# Sheet1.net
KiCad netlist of a schematic drawn in Altium Designer
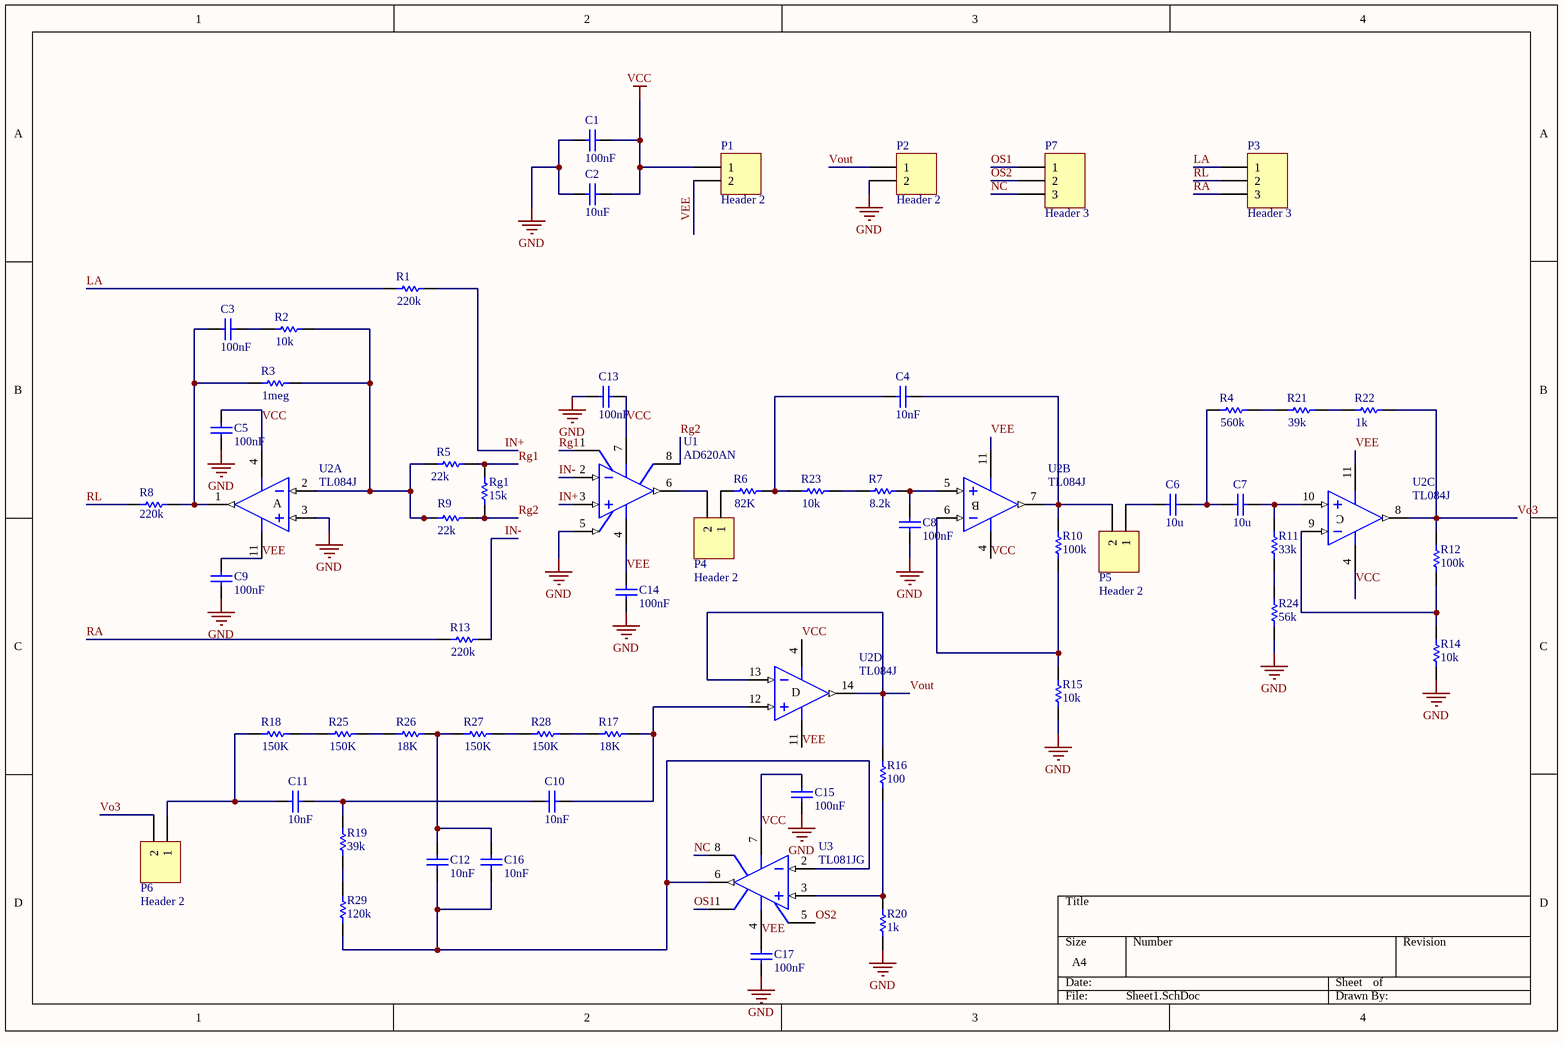
[diagram p0: Sheet1.SchDoc]

(export (version "E")
  (design (tool "Eeschema 10.0.6"))
  (components
    (comp (ref "C1")
      (value "100nF")
      (footprint "RAD-0.3")
      (description "Capacitor")
      (fields (field (name "PUBLISHER") "Altium Limited"))
      (libsource (lib "Miscellaneous Devices") (part "Cap"))
    )
    (comp (ref "C2")
      (value "10uF")
      (footprint "RAD-0.3")
      (description "Capacitor")
      (fields (field (name "PUBLISHER") "Altium Limited"))
      (libsource (lib "Miscellaneous Devices") (part "Cap"))
    )
    (comp (ref "C3")
      (value "100nF")
      (footprint "RAD-0.3")
      (description "Capacitor")
      (fields (field (name "PUBLISHER") "Altium Limited"))
      (libsource (lib "Miscellaneous Devices") (part "Cap"))
    )
    (comp (ref "C4")
      (value "10nF")
      (footprint "RAD-0.3")
      (description "Capacitor")
      (fields (field (name "Comment") "Cap") (field (name "PUBLISHER") "Altium Limited"))
      (libsource (lib "Miscellaneous Devices") (part "Cap"))
    )
    (comp (ref "C5")
      (value "100nF")
      (footprint "RAD-0.3")
      (description "Capacitor")
      (fields (field (name "Comment") "Cap") (field (name "PUBLISHER") "Altium Limited"))
      (libsource (lib "Miscellaneous Devices") (part "Cap"))
    )
    (comp (ref "C6")
      (value "10u")
      (footprint "RAD-0.3")
      (description "Capacitor")
      (fields (field (name "Comment") "Cap") (field (name "PUBLISHER") "Altium Limited"))
      (libsource (lib "Miscellaneous Devices") (part "Cap"))
    )
    (comp (ref "C7")
      (value "10u")
      (footprint "RAD-0.3")
      (description "Capacitor")
      (fields (field (name "Comment") "Cap") (field (name "PUBLISHER") "Altium Limited"))
      (libsource (lib "Miscellaneous Devices") (part "Cap"))
    )
    (comp (ref "C8")
      (value "100nF")
      (footprint "RAD-0.3")
      (description "Capacitor")
      (fields (field (name "Comment") "Cap") (field (name "PUBLISHER") "Altium Limited"))
      (libsource (lib "Miscellaneous Devices") (part "Cap"))
    )
    (comp (ref "C9")
      (value "100nF")
      (footprint "RAD-0.3")
      (description "Capacitor")
      (fields (field (name "Comment") "Cap") (field (name "PUBLISHER") "Altium Limited"))
      (libsource (lib "Miscellaneous Devices") (part "Cap"))
    )
    (comp (ref "C10")
      (value "10nF")
      (footprint "RAD-0.3")
      (description "Capacitor")
      (fields (field (name "Comment") "Cap") (field (name "PUBLISHER") "Altium Limited"))
      (libsource (lib "Miscellaneous Devices") (part "Cap"))
    )
    (comp (ref "C11")
      (value "10nF")
      (footprint "RAD-0.3")
      (description "Capacitor")
      (fields (field (name "Comment") "Cap") (field (name "PUBLISHER") "Altium Limited"))
      (libsource (lib "Miscellaneous Devices") (part "Cap"))
    )
    (comp (ref "C12")
      (value "10nF")
      (footprint "RAD-0.3")
      (description "Capacitor")
      (fields (field (name "Comment") "Cap") (field (name "PUBLISHER") "Altium Limited"))
      (libsource (lib "Miscellaneous Devices") (part "Cap"))
    )
    (comp (ref "C13")
      (value "100nF")
      (footprint "RAD-0.3")
      (description "Capacitor")
      (fields (field (name "PUBLISHER") "Altium Limited"))
      (libsource (lib "Miscellaneous Devices") (part "Cap"))
    )
    (comp (ref "C14")
      (value "100nF")
      (footprint "RAD-0.3")
      (description "Capacitor")
      (fields (field (name "Comment") "Cap") (field (name "PUBLISHER") "Altium Limited"))
      (libsource (lib "Miscellaneous Devices") (part "Cap"))
    )
    (comp (ref "C15")
      (value "100nF")
      (footprint "RAD-0.3")
      (description "Capacitor")
      (fields (field (name "Comment") "Cap") (field (name "PUBLISHER") "Altium Limited"))
      (libsource (lib "Miscellaneous Devices") (part "Cap"))
    )
    (comp (ref "C16")
      (value "10nF")
      (footprint "RAD-0.3")
      (description "Capacitor")
      (fields (field (name "Comment") "Cap") (field (name "PUBLISHER") "Altium Limited"))
      (libsource (lib "Miscellaneous Devices") (part "Cap"))
    )
    (comp (ref "C17")
      (value "100nF")
      (footprint "RAD-0.3")
      (description "Capacitor")
      (fields (field (name "Comment") "Cap") (field (name "PUBLISHER") "Altium Limited"))
      (libsource (lib "Miscellaneous Devices") (part "Cap"))
    )
    (comp (ref "P1")
      (value "Header 2")
      (footprint "HDR1X2")
      (description "Header, 2-Pin")
      (fields (field (name "PUBLISHER") "Altium Limited"))
      (libsource (lib "") (part "Header 2_1"))
    )
    (comp (ref "P2")
      (value "Header 2")
      (footprint "HDR1X2")
      (description "Header, 2-Pin")
      (fields (field (name "PUBLISHER") "Altium Limited"))
      (libsource (lib "") (part "Header 2_1"))
    )
    (comp (ref "P3")
      (value "Header 3")
      (footprint "HDR1X3")
      (description "Header, 3-Pin")
      (fields (field (name "PUBLISHER") "Altium Limited"))
      (libsource (lib "Miscellaneous Connectors") (part "Header 3"))
    )
    (comp (ref "P4")
      (value "Header 2")
      (footprint "HDR1X2")
      (description "Header, 2-Pin")
      (fields (field (name "PUBLISHER") "Altium Limited"))
      (libsource (lib "Miscellaneous Connectors") (part "Header 2"))
    )
    (comp (ref "P5")
      (value "Header 2")
      (footprint "HDR1X2")
      (description "Header, 2-Pin")
      (fields (field (name "PUBLISHER") "Altium Limited"))
      (libsource (lib "Miscellaneous Connectors") (part "Header 2"))
    )
    (comp (ref "P6")
      (value "Header 2")
      (footprint "HDR1X2")
      (description "Header, 2-Pin")
      (fields (field (name "PUBLISHER") "Altium Limited"))
      (libsource (lib "Miscellaneous Connectors") (part "Header 2"))
    )
    (comp (ref "P7")
      (value "Header 3")
      (footprint "HDR1X3")
      (description "Header, 3-Pin")
      (fields (field (name "PUBLISHER") "Altium Limited"))
      (libsource (lib "Miscellaneous Connectors") (part "Header 3"))
    )
    (comp (ref "R1")
      (value "220k")
      (footprint "AXIAL-0.3")
      (description "Resistor")
      (fields (field (name "Comment") "Res1") (field (name "PUBLISHER") "Altium Limited"))
      (libsource (lib "Miscellaneous Devices") (part "Res1"))
    )
    (comp (ref "R2")
      (value "10k")
      (footprint "AXIAL-0.3")
      (description "Resistor")
      (fields (field (name "Comment") "Res1") (field (name "PUBLISHER") "Altium Limited"))
      (libsource (lib "Miscellaneous Devices") (part "Res1"))
    )
    (comp (ref "R3")
      (value "1meg")
      (footprint "AXIAL-0.3")
      (description "Resistor")
      (fields (field (name "Comment") "Res1") (field (name "PUBLISHER") "Altium Limited"))
      (libsource (lib "Miscellaneous Devices") (part "Res1"))
    )
    (comp (ref "R4")
      (value "560k")
      (footprint "AXIAL-0.3")
      (description "Resistor")
      (fields (field (name "Comment") "Res1") (field (name "PUBLISHER") "Altium Limited"))
      (libsource (lib "Miscellaneous Devices") (part "Res1"))
    )
    (comp (ref "R5")
      (value "22k")
      (footprint "AXIAL-0.3")
      (description "Resistor")
      (fields (field (name "Comment") "Res1") (field (name "PUBLISHER") "Altium Limited"))
      (libsource (lib "Miscellaneous Devices") (part "Res1"))
    )
    (comp (ref "R6")
      (value "82K")
      (footprint "AXIAL-0.3")
      (description "Resistor")
      (fields (field (name "Comment") "Res1") (field (name "PUBLISHER") "Altium Limited"))
      (libsource (lib "Miscellaneous Devices") (part "Res1"))
    )
    (comp (ref "R7")
      (value "8.2k")
      (footprint "AXIAL-0.3")
      (description "Resistor")
      (fields (field (name "Comment") "Res1") (field (name "PUBLISHER") "Altium Limited"))
      (libsource (lib "Miscellaneous Devices") (part "Res1"))
    )
    (comp (ref "R8")
      (value "220k")
      (footprint "AXIAL-0.3")
      (description "Resistor")
      (fields (field (name "Comment") "Res1") (field (name "PUBLISHER") "Altium Limited"))
      (libsource (lib "Miscellaneous Devices") (part "Res1"))
    )
    (comp (ref "R9")
      (value "22k")
      (footprint "AXIAL-0.3")
      (description "Resistor")
      (fields (field (name "Comment") "Res1") (field (name "PUBLISHER") "Altium Limited"))
      (libsource (lib "Miscellaneous Devices") (part "Res1"))
    )
    (comp (ref "R10")
      (value "100k")
      (footprint "AXIAL-0.3")
      (description "Resistor")
      (fields (field (name "Comment") "Res1") (field (name "PUBLISHER") "Altium Limited"))
      (libsource (lib "Miscellaneous Devices") (part "Res1"))
    )
    (comp (ref "R11")
      (value "33k")
      (footprint "AXIAL-0.3")
      (description "Resistor")
      (fields (field (name "Comment") "Res1") (field (name "PUBLISHER") "Altium Limited"))
      (libsource (lib "Miscellaneous Devices") (part "Res1"))
    )
    (comp (ref "R12")
      (value "100k")
      (footprint "AXIAL-0.3")
      (description "Resistor")
      (fields (field (name "Comment") "Res1") (field (name "PUBLISHER") "Altium Limited"))
      (libsource (lib "Miscellaneous Devices") (part "Res1"))
    )
    (comp (ref "R13")
      (value "220k")
      (footprint "AXIAL-0.3")
      (description "Resistor")
      (fields (field (name "Comment") "Res1") (field (name "PUBLISHER") "Altium Limited"))
      (libsource (lib "Miscellaneous Devices") (part "Res1"))
    )
    (comp (ref "R14")
      (value "10k")
      (footprint "AXIAL-0.3")
      (description "Resistor")
      (fields (field (name "Comment") "Res1") (field (name "PUBLISHER") "Altium Limited"))
      (libsource (lib "Miscellaneous Devices") (part "Res1"))
    )
    (comp (ref "R15")
      (value "10k")
      (footprint "AXIAL-0.3")
      (description "Resistor")
      (fields (field (name "Comment") "Res1") (field (name "PUBLISHER") "Altium Limited"))
      (libsource (lib "Miscellaneous Devices") (part "Res1"))
    )
    (comp (ref "R16")
      (value "100")
      (footprint "AXIAL-0.3")
      (description "Resistor")
      (fields (field (name "Comment") "Res1") (field (name "PUBLISHER") "Altium Limited"))
      (libsource (lib "Miscellaneous Devices") (part "Res1"))
    )
    (comp (ref "R17")
      (value "18K")
      (footprint "AXIAL-0.3")
      (description "Resistor")
      (fields (field (name "Comment") "Res1") (field (name "PUBLISHER") "Altium Limited"))
      (libsource (lib "Miscellaneous Devices") (part "Res1"))
    )
    (comp (ref "R18")
      (value "150K")
      (footprint "AXIAL-0.3")
      (description "Resistor")
      (fields (field (name "Comment") "Res1") (field (name "PUBLISHER") "Altium Limited"))
      (libsource (lib "Miscellaneous Devices") (part "Res1"))
    )
    (comp (ref "R19")
      (value "39k")
      (footprint "AXIAL-0.3")
      (description "Resistor")
      (fields (field (name "Comment") "Res1") (field (name "PUBLISHER") "Altium Limited"))
      (libsource (lib "Miscellaneous Devices") (part "Res1"))
    )
    (comp (ref "R20")
      (value "1k")
      (footprint "AXIAL-0.3")
      (description "Resistor")
      (fields (field (name "Comment") "Res1") (field (name "PUBLISHER") "Altium Limited"))
      (libsource (lib "Miscellaneous Devices") (part "Res1"))
    )
    (comp (ref "R21")
      (value "39k")
      (footprint "AXIAL-0.3")
      (description "Resistor")
      (fields (field (name "Comment") "Res1") (field (name "PUBLISHER") "Altium Limited"))
      (libsource (lib "Miscellaneous Devices") (part "Res1"))
    )
    (comp (ref "R22")
      (value "1k")
      (footprint "AXIAL-0.3")
      (description "Resistor")
      (fields (field (name "Comment") "Res1") (field (name "PUBLISHER") "Altium Limited"))
      (libsource (lib "Miscellaneous Devices") (part "Res1"))
    )
    (comp (ref "R23")
      (value "10k")
      (footprint "AXIAL-0.3")
      (description "Resistor")
      (fields (field (name "Comment") "Res1") (field (name "PUBLISHER") "Altium Limited"))
      (libsource (lib "Miscellaneous Devices") (part "Res1"))
    )
    (comp (ref "R24")
      (value "56k")
      (footprint "AXIAL-0.3")
      (description "Resistor")
      (fields (field (name "Comment") "Res1") (field (name "PUBLISHER") "Altium Limited"))
      (libsource (lib "Miscellaneous Devices") (part "Res1"))
    )
    (comp (ref "R25")
      (value "150K")
      (footprint "AXIAL-0.3")
      (description "Resistor")
      (fields (field (name "Comment") "Res1") (field (name "PUBLISHER") "Altium Limited"))
      (libsource (lib "Miscellaneous Devices") (part "Res1"))
    )
    (comp (ref "R26")
      (value "18K")
      (footprint "AXIAL-0.3")
      (description "Resistor")
      (fields (field (name "Comment") "Res1") (field (name "PUBLISHER") "Altium Limited"))
      (libsource (lib "Miscellaneous Devices") (part "Res1"))
    )
    (comp (ref "R27")
      (value "150K")
      (footprint "AXIAL-0.3")
      (description "Resistor")
      (fields (field (name "Comment") "Res1") (field (name "PUBLISHER") "Altium Limited"))
      (libsource (lib "Miscellaneous Devices") (part "Res1"))
    )
    (comp (ref "R28")
      (value "150K")
      (footprint "AXIAL-0.3")
      (description "Resistor")
      (fields (field (name "Comment") "Res1") (field (name "PUBLISHER") "Altium Limited"))
      (libsource (lib "Miscellaneous Devices") (part "Res1"))
    )
    (comp (ref "R29")
      (value "120k")
      (footprint "AXIAL-0.3")
      (description "Resistor")
      (fields (field (name "Comment") "Res1") (field (name "PUBLISHER") "Altium Limited"))
      (libsource (lib "Miscellaneous Devices") (part "Res1"))
    )
    (comp (ref "Rg1")
      (value "15k")
      (footprint "AXIAL-0.3")
      (description "Resistor")
      (fields (field (name "Comment") "Res1") (field (name "PUBLISHER") "Altium Limited"))
      (libsource (lib "Miscellaneous Devices") (part "Res1"))
    )
    (comp (ref "U1")
      (value "AD620AN")
      (footprint "N-8")
      (description "Low-Cost, Low-Power Instrumentation Amplifier")
      (fields (field (name "PUBLISHER") "Altium Limited"))
      (libsource (lib "AD Instrumentation Amplifier") (part "AD620AN"))
    )
    (comp (ref "U2")
      (value "TL084J")
      (footprint "J014")
      (description "JFET-Input Operational Amplifier")
      (fields (field (name "PUBLISHER") "Altium Limited"))
      (libsource (lib "TI Operational Amplifier") (part "TL084J"))
    )
    (comp (ref "U3")
      (value "TL081JG")
      (footprint "JG008")
      (description "JFET-Input Operational Amplifier")
      (fields (field (name "PUBLISHER") "Altium Limited"))
      (libsource (lib "TI Operational Amplifier") (part "TL081JG"))
    )
  )
  (nets
    (net (code "1") (name "/IN+") (class "Default")
      (node (ref "R1") (pin "2") (pinfunction "2_2") (pintype "passive"))
      (node (ref "U1") (pin "3") (pinfunction "+IN_3") (pintype "input"))
    )
    (net (code "2") (name "/IN-") (class "Default")
      (node (ref "R13") (pin "2") (pinfunction "2_2") (pintype "passive"))
      (node (ref "U1") (pin "2") (pinfunction "-IN_2") (pintype "input"))
    )
    (net (code "3") (name "/LA") (class "Default")
      (node (ref "P3") (pin "1") (pinfunction "1_1") (pintype "passive"))
      (node (ref "R1") (pin "1") (pinfunction "1_1") (pintype "passive"))
    )
    (net (code "4") (name "/NC") (class "Default")
      (node (ref "P7") (pin "3") (pinfunction "3_3") (pintype "passive"))
      (node (ref "U3") (pin "8") (pinfunction "NC_8") (pintype "passive"))
    )
    (net (code "5") (name "/OS1") (class "Default")
      (node (ref "P7") (pin "1") (pinfunction "1_1") (pintype "passive"))
      (node (ref "U3") (pin "1") (pinfunction "OS_TRIM_1") (pintype "passive"))
    )
    (net (code "6") (name "/OS2") (class "Default")
      (node (ref "P7") (pin "2") (pinfunction "2_2") (pintype "passive"))
      (node (ref "U3") (pin "5") (pinfunction "OS_TRIM_5") (pintype "passive"))
    )
    (net (code "7") (name "/RA") (class "Default")
      (node (ref "P3") (pin "3") (pinfunction "3_3") (pintype "passive"))
      (node (ref "R13") (pin "1") (pinfunction "1_1") (pintype "passive"))
    )
    (net (code "8") (name "/RL") (class "Default")
      (node (ref "P3") (pin "2") (pinfunction "2_2") (pintype "passive"))
      (node (ref "R8") (pin "2") (pinfunction "2_2") (pintype "passive"))
    )
    (net (code "9") (name "/Rg1") (class "Default")
      (node (ref "R5") (pin "2") (pinfunction "2_2") (pintype "passive"))
      (node (ref "Rg1") (pin "2") (pinfunction "2_2") (pintype "passive"))
      (node (ref "U1") (pin "1") (pinfunction "RG_1") (pintype "passive"))
    )
    (net (code "10") (name "/Rg2") (class "Default")
      (node (ref "R9") (pin "2") (pinfunction "2_2") (pintype "passive"))
      (node (ref "Rg1") (pin "1") (pinfunction "1_1") (pintype "passive"))
      (node (ref "U1") (pin "8") (pinfunction "RG_8") (pintype "passive"))
    )
    (net (code "11") (name "/VEE") (class "Default")
      (node (ref "C14") (pin "2") (pinfunction "2_2") (pintype "passive"))
      (node (ref "C17") (pin "2") (pinfunction "2_2") (pintype "passive"))
      (node (ref "C9") (pin "2") (pinfunction "2_2") (pintype "passive"))
      (node (ref "P1") (pin "2") (pinfunction "2_2") (pintype "passive"))
      (node (ref "U1") (pin "4") (pinfunction "V-_4") (pintype "power_in"))
      (node (ref "U2") (pin "11") (pinfunction "V-_11") (pintype "power_in"))
      (node (ref "U3") (pin "4") (pinfunction "V-_4") (pintype "power_in"))
    )
    (net (code "12") (name "/Vo3") (class "Default")
      (node (ref "P6") (pin "2") (pinfunction "2_2") (pintype "passive"))
      (node (ref "R12") (pin "2") (pinfunction "2_2") (pintype "passive"))
      (node (ref "R22") (pin "2") (pinfunction "2_2") (pintype "passive"))
      (node (ref "U2") (pin "8") (pinfunction "OUT_8") (pintype "output"))
    )
    (net (code "13") (name "/Vout") (class "Default")
      (node (ref "P2") (pin "1") (pinfunction "1_1") (pintype "passive"))
      (node (ref "R16") (pin "2") (pinfunction "2_2") (pintype "passive"))
      (node (ref "U2") (pin "13") (pinfunction "IN-_13") (pintype "input"))
      (node (ref "U2") (pin "14") (pinfunction "OUT_14") (pintype "output"))
    )
    (net (code "14") (name "GND") (class "Default")
      (node (ref "C1") (pin "1") (pinfunction "1_1") (pintype "passive"))
      (node (ref "C13") (pin "1") (pinfunction "1_1") (pintype "passive"))
      (node (ref "C14") (pin "1") (pinfunction "1_1") (pintype "passive"))
      (node (ref "C15") (pin "1") (pinfunction "1_1") (pintype "passive"))
      (node (ref "C17") (pin "1") (pinfunction "1_1") (pintype "passive"))
      (node (ref "C2") (pin "1") (pinfunction "1_1") (pintype "passive"))
      (node (ref "C5") (pin "1") (pinfunction "1_1") (pintype "passive"))
      (node (ref "C8") (pin "1") (pinfunction "1_1") (pintype "passive"))
      (node (ref "C9") (pin "1") (pinfunction "1_1") (pintype "passive"))
      (node (ref "P2") (pin "2") (pinfunction "2_2") (pintype "passive"))
      (node (ref "R14") (pin "1") (pinfunction "1_1") (pintype "passive"))
      (node (ref "R15") (pin "1") (pinfunction "1_1") (pintype "passive"))
      (node (ref "R20") (pin "1") (pinfunction "1_1") (pintype "passive"))
      (node (ref "R24") (pin "1") (pinfunction "1_1") (pintype "passive"))
      (node (ref "U1") (pin "5") (pinfunction "REF_5") (pintype "input"))
      (node (ref "U2") (pin "3") (pinfunction "IN+_3") (pintype "input"))
    )
    (net (code "15") (name "Net-(C3-Pad2)") (class "Default")
      (node (ref "C3") (pin "2") (pinfunction "2_2") (pintype "passive"))
      (node (ref "R2") (pin "1") (pinfunction "1_1") (pintype "passive"))
    )
    (net (code "16") (name "Net-(C4-Pad2)") (class "Default")
      (node (ref "C4") (pin "2") (pinfunction "2_2") (pintype "passive"))
      (node (ref "R23") (pin "1") (pinfunction "1_1") (pintype "passive"))
      (node (ref "R6") (pin "2") (pinfunction "2_2") (pintype "passive"))
    )
    (net (code "17") (name "Net-(C6-Pad1)") (class "Default")
      (node (ref "C6") (pin "1") (pinfunction "1_1") (pintype "passive"))
      (node (ref "C7") (pin "2") (pinfunction "2_2") (pintype "passive"))
      (node (ref "R4") (pin "1") (pinfunction "1_1") (pintype "passive"))
    )
    (net (code "18") (name "Net-(C6-Pad2)") (class "Default")
      (node (ref "C6") (pin "2") (pinfunction "2_2") (pintype "passive"))
      (node (ref "P5") (pin "1") (pinfunction "1_1") (pintype "passive"))
    )
    (net (code "19") (name "Net-(C10-Pad2)") (class "Default")
      (node (ref "C10") (pin "2") (pinfunction "2_2") (pintype "passive"))
      (node (ref "C11") (pin "1") (pinfunction "1_1") (pintype "passive"))
      (node (ref "R19") (pin "2") (pinfunction "2_2") (pintype "passive"))
    )
    (net (code "20") (name "Net-(C11-Pad2)") (class "Default")
      (node (ref "C11") (pin "2") (pinfunction "2_2") (pintype "passive"))
      (node (ref "P6") (pin "1") (pinfunction "1_1") (pintype "passive"))
      (node (ref "R18") (pin "1") (pinfunction "1_1") (pintype "passive"))
    )
    (net (code "21") (name "Net-(C12-Pad1)") (class "Default")
      (node (ref "C12") (pin "1") (pinfunction "1_1") (pintype "passive"))
      (node (ref "C16") (pin "1") (pinfunction "1_1") (pintype "passive"))
      (node (ref "R26") (pin "2") (pinfunction "2_2") (pintype "passive"))
      (node (ref "R27") (pin "1") (pinfunction "1_1") (pintype "passive"))
    )
    (net (code "22") (name "Net-(P4-Pad1)") (class "Default")
      (node (ref "P4") (pin "1") (pinfunction "1_1") (pintype "passive"))
      (node (ref "R6") (pin "1") (pinfunction "1_1") (pintype "passive"))
    )
    (net (code "23") (name "Net-(R11-Pad1)") (class "Default")
      (node (ref "R11") (pin "1") (pinfunction "1_1") (pintype "passive"))
      (node (ref "R24") (pin "2") (pinfunction "2_2") (pintype "passive"))
    )
    (net (code "24") (name "Net-(R17-Pad1)") (class "Default")
      (node (ref "R17") (pin "1") (pinfunction "1_1") (pintype "passive"))
      (node (ref "R28") (pin "2") (pinfunction "2_2") (pintype "passive"))
    )
    (net (code "25") (name "Net-(R18-Pad2)") (class "Default")
      (node (ref "R18") (pin "2") (pinfunction "2_2") (pintype "passive"))
      (node (ref "R25") (pin "1") (pinfunction "1_1") (pintype "passive"))
    )
    (net (code "26") (name "Net-(R19-Pad1)") (class "Default")
      (node (ref "R19") (pin "1") (pinfunction "1_1") (pintype "passive"))
      (node (ref "R29") (pin "2") (pinfunction "2_2") (pintype "passive"))
    )
    (net (code "27") (name "Net-(R21-Pad1)") (class "Default")
      (node (ref "R21") (pin "1") (pinfunction "1_1") (pintype "passive"))
      (node (ref "R4") (pin "2") (pinfunction "2_2") (pintype "passive"))
    )
    (net (code "28") (name "Net-(R21-Pad2)") (class "Default")
      (node (ref "R21") (pin "2") (pinfunction "2_2") (pintype "passive"))
      (node (ref "R22") (pin "1") (pinfunction "1_1") (pintype "passive"))
    )
    (net (code "29") (name "Net-(R23-Pad2)") (class "Default")
      (node (ref "R23") (pin "2") (pinfunction "2_2") (pintype "passive"))
      (node (ref "R7") (pin "1") (pinfunction "1_1") (pintype "passive"))
    )
    (net (code "30") (name "Net-(R25-Pad2)") (class "Default")
      (node (ref "R25") (pin "2") (pinfunction "2_2") (pintype "passive"))
      (node (ref "R26") (pin "1") (pinfunction "1_1") (pintype "passive"))
    )
    (net (code "31") (name "Net-(R27-Pad2)") (class "Default")
      (node (ref "R27") (pin "2") (pinfunction "2_2") (pintype "passive"))
      (node (ref "R28") (pin "1") (pinfunction "1_1") (pintype "passive"))
    )
    (net (code "32") (name "Net-(U1-OUT)") (class "Default")
      (node (ref "P4") (pin "2") (pinfunction "2_2") (pintype "passive"))
      (node (ref "U1") (pin "6") (pinfunction "OUT_6") (pintype "output"))
    )
    (net (code "33") (name "Net-(U2A-IN-)") (class "Default")
      (node (ref "R2") (pin "2") (pinfunction "2_2") (pintype "passive"))
      (node (ref "R3") (pin "2") (pinfunction "2_2") (pintype "passive"))
      (node (ref "R5") (pin "1") (pinfunction "1_1") (pintype "passive"))
      (node (ref "R9") (pin "1") (pinfunction "1_1") (pintype "passive"))
      (node (ref "U2") (pin "2") (pinfunction "IN-_2") (pintype "input"))
    )
    (net (code "34") (name "Net-(U2A-OUT)") (class "Default")
      (node (ref "C3") (pin "1") (pinfunction "1_1") (pintype "passive"))
      (node (ref "R3") (pin "1") (pinfunction "1_1") (pintype "passive"))
      (node (ref "R8") (pin "1") (pinfunction "1_1") (pintype "passive"))
      (node (ref "U2") (pin "1") (pinfunction "OUT_1") (pintype "output"))
    )
    (net (code "35") (name "Net-(U2B-IN+)") (class "Default")
      (node (ref "C8") (pin "2") (pinfunction "2_2") (pintype "passive"))
      (node (ref "R7") (pin "2") (pinfunction "2_2") (pintype "passive"))
      (node (ref "U2") (pin "5") (pinfunction "IN+_5") (pintype "input"))
    )
    (net (code "36") (name "Net-(U2B-IN-)") (class "Default")
      (node (ref "R10") (pin "1") (pinfunction "1_1") (pintype "passive"))
      (node (ref "R15") (pin "2") (pinfunction "2_2") (pintype "passive"))
      (node (ref "U2") (pin "6") (pinfunction "IN-_6") (pintype "input"))
    )
    (net (code "37") (name "Net-(U2B-OUT)") (class "Default")
      (node (ref "C4") (pin "1") (pinfunction "1_1") (pintype "passive"))
      (node (ref "P5") (pin "2") (pinfunction "2_2") (pintype "passive"))
      (node (ref "R10") (pin "2") (pinfunction "2_2") (pintype "passive"))
      (node (ref "U2") (pin "7") (pinfunction "OUT_7") (pintype "output"))
    )
    (net (code "38") (name "Net-(U2C-IN+)") (class "Default")
      (node (ref "C7") (pin "1") (pinfunction "1_1") (pintype "passive"))
      (node (ref "R11") (pin "2") (pinfunction "2_2") (pintype "passive"))
      (node (ref "U2") (pin "10") (pinfunction "IN+_10") (pintype "input"))
    )
    (net (code "39") (name "Net-(U2C-IN-)") (class "Default")
      (node (ref "R12") (pin "1") (pinfunction "1_1") (pintype "passive"))
      (node (ref "R14") (pin "2") (pinfunction "2_2") (pintype "passive"))
      (node (ref "U2") (pin "9") (pinfunction "IN-_9") (pintype "input"))
    )
    (net (code "40") (name "Net-(U2D-IN+)") (class "Default")
      (node (ref "C10") (pin "1") (pinfunction "1_1") (pintype "passive"))
      (node (ref "R17") (pin "2") (pinfunction "2_2") (pintype "passive"))
      (node (ref "U2") (pin "12") (pinfunction "IN+_12") (pintype "input"))
    )
    (net (code "41") (name "Net-(U3-IN+)") (class "Default")
      (node (ref "R16") (pin "1") (pinfunction "1_1") (pintype "passive"))
      (node (ref "R20") (pin "2") (pinfunction "2_2") (pintype "passive"))
      (node (ref "U3") (pin "3") (pinfunction "IN+_3") (pintype "input"))
    )
    (net (code "42") (name "Net-(U3-IN-)") (class "Default")
      (node (ref "C12") (pin "2") (pinfunction "2_2") (pintype "passive"))
      (node (ref "C16") (pin "2") (pinfunction "2_2") (pintype "passive"))
      (node (ref "R29") (pin "1") (pinfunction "1_1") (pintype "passive"))
      (node (ref "U3") (pin "2") (pinfunction "IN-_2") (pintype "input"))
      (node (ref "U3") (pin "6") (pinfunction "OUT_6") (pintype "output"))
    )
    (net (code "43") (name "VCC") (class "Default")
      (node (ref "C1") (pin "2") (pinfunction "2_2") (pintype "passive"))
      (node (ref "C13") (pin "2") (pinfunction "2_2") (pintype "passive"))
      (node (ref "C15") (pin "2") (pinfunction "2_2") (pintype "passive"))
      (node (ref "C2") (pin "2") (pinfunction "2_2") (pintype "passive"))
      (node (ref "C5") (pin "2") (pinfunction "2_2") (pintype "passive"))
      (node (ref "P1") (pin "1") (pinfunction "1_1") (pintype "passive"))
      (node (ref "U1") (pin "7") (pinfunction "V+_7") (pintype "power_in"))
      (node (ref "U2") (pin "4") (pinfunction "V+_4") (pintype "power_in"))
      (node (ref "U3") (pin "7") (pinfunction "V+_7") (pintype "power_in"))
    )
  )
)
